# Beta0_1_5_Schematic_diagram.net
KiCad netlist of a schematic drawn in Altium Designer
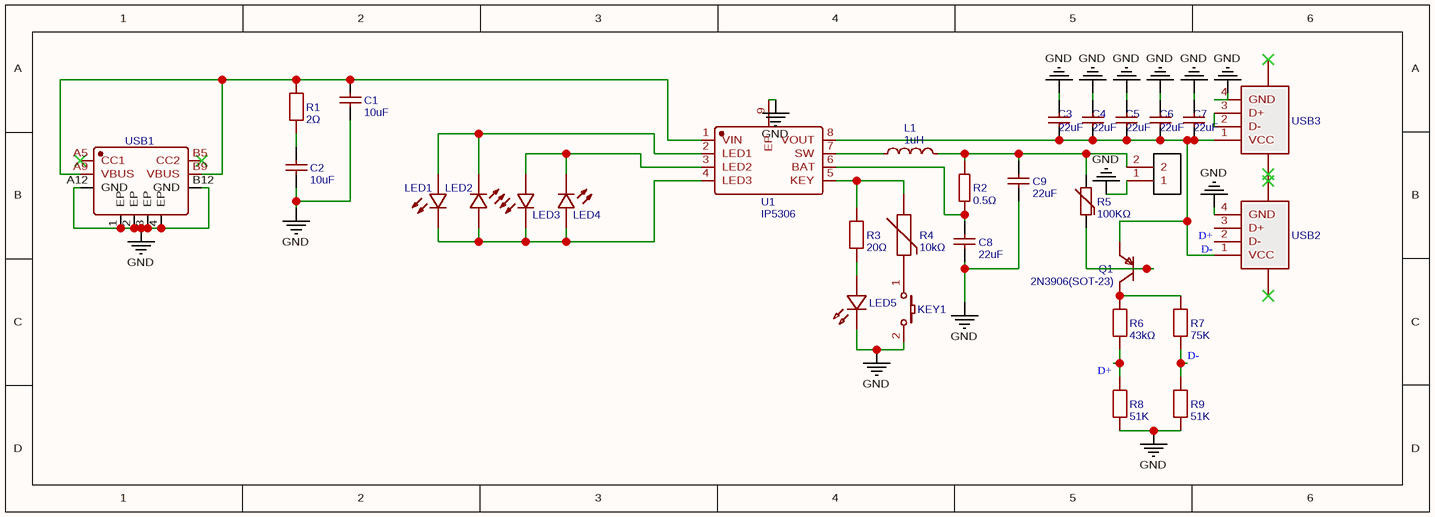
[diagram p0: Beta0.1.5 Schematic diagram.schdoc]

(export (version "E")
  (design (tool "Eeschema 10.0.6"))
  (components
    (comp (ref "C1")
      (value "10uF")
      (fields
        (field (name "BOM_MANUFACTURER PART") "CL31A106KBHNNNE")
        (field (name "BOM_SUPPLIER PART") "C13585")
      )
      (libsource (lib "altium-import") (part "root_3_10uF_"))
    )
    (comp (ref "C2")
      (value "10uF")
      (fields
        (field (name "BOM_MANUFACTURER PART") "CL31A106KBHNNNE")
        (field (name "BOM_SUPPLIER PART") "C13585")
      )
      (libsource (lib "altium-import") (part "root_3_10uF_"))
    )
    (comp (ref "C3")
      (value "22uF")
      (fields
        (field (name "BOM_MANUFACTURER PART") "CL31A226KPHNNNE")
        (field (name "BOM_SUPPLIER PART") "C5672")
      )
      (libsource (lib "altium-import") (part "root_1_22uF_"))
    )
    (comp (ref "C4")
      (value "22uF")
      (fields
        (field (name "BOM_MANUFACTURER PART") "CL31A226KPHNNNE")
        (field (name "BOM_SUPPLIER PART") "C5672")
      )
      (libsource (lib "altium-import") (part "root_1_22uF_"))
    )
    (comp (ref "C5")
      (value "22uF")
      (fields
        (field (name "BOM_MANUFACTURER PART") "CL31A226KPHNNNE")
        (field (name "BOM_SUPPLIER PART") "C5672")
      )
      (libsource (lib "altium-import") (part "root_1_22uF_"))
    )
    (comp (ref "C6")
      (value "22uF")
      (fields
        (field (name "BOM_MANUFACTURER PART") "CL31A226KPHNNNE")
        (field (name "BOM_SUPPLIER PART") "C5672")
      )
      (libsource (lib "altium-import") (part "root_1_22uF_"))
    )
    (comp (ref "C7")
      (value "22uF")
      (fields
        (field (name "BOM_MANUFACTURER PART") "CL31A226KPHNNNE")
        (field (name "BOM_SUPPLIER PART") "C5672")
      )
      (libsource (lib "altium-import") (part "root_1_22uF_"))
    )
    (comp (ref "C8")
      (value "22uF")
      (fields
        (field (name "BOM_MANUFACTURER PART") "CL31A226KPHNNNE")
        (field (name "BOM_SUPPLIER PART") "C5672")
      )
      (libsource (lib "altium-import") (part "root_1_22uF_"))
    )
    (comp (ref "C9")
      (value "22uF")
      (fields
        (field (name "BOM_MANUFACTURER PART") "CL31A226KPHNNNE")
        (field (name "BOM_SUPPLIER PART") "C5672")
      )
      (libsource (lib "altium-import") (part "root_1_22uF_"))
    )
    (comp (ref "CN1")
      (value "254010-02A-T0P")
      (fields (field (name "BOM_SUPPLIER PART") "C181912") (field (name "CONTRIBUTOR") "LCSC"))
      (libsource (lib "altium-import") (part "root_1_254010-02A-T0P_"))
    )
    (comp (ref "KEY1")
      (value "K2-3.6×6.1_SMD")
      (fields
        (field (name "BOM_SUPPLIER PART") "C118141")
        (field (name "BOM_MANUFACTURER PART") "K2-1107ST-A4SW-06")
        (field (name "CONTRIBUTOR") "LCEDA_Lib")
      )
      (libsource (lib "altium-import") (part "root_3_K2-3.6×6.1_SMD_"))
    )
    (comp (ref "L1")
      (value "1uH")
      (fields
        (field (name "BOM_MANUFACTURER PART") "SPM6530T-1R0M120")
        (field (name "BOM_SUPPLIER PART") "C87572")
      )
      (libsource (lib "altium-import") (part "root_0_1uH_"))
    )
    (comp (ref "LED1")
      (value "LED1")
      (fields
        (field (name "BOM_MANUFACTURER PART") "FC-DA1608HRK-620D")
        (field (name "BOM_SUPPLIER PART") "C84263")
      )
      (libsource (lib "altium-import") (part "root_3_LED1_"))
    )
    (comp (ref "LED2")
      (value "LED1")
      (fields
        (field (name "BOM_MANUFACTURER PART") "FC-DA1608HRK-620D")
        (field (name "BOM_SUPPLIER PART") "C84263")
      )
      (libsource (lib "altium-import") (part "root_1_LED1_"))
    )
    (comp (ref "LED3")
      (value "LED1")
      (fields
        (field (name "BOM_MANUFACTURER PART") "FC-DA1608HRK-620D")
        (field (name "BOM_SUPPLIER PART") "C84263")
      )
      (libsource (lib "altium-import") (part "root_3_LED1_"))
    )
    (comp (ref "LED4")
      (value "LED1")
      (fields
        (field (name "BOM_MANUFACTURER PART") "FC-DA1608HRK-620D")
        (field (name "BOM_SUPPLIER PART") "C84263")
      )
      (libsource (lib "altium-import") (part "root_1_LED1_"))
    )
    (comp (ref "LED5")
      (value "TZ-P2-1206WYCS2-0.9T")
      (fields (field (name "BOM_SUPPLIER PART") "C779809") (field (name "CONTRIBUTOR") "LCSC"))
      (libsource (lib "altium-import") (part "root_1_TZ-P2-1206WYCS2-0.9T_"))
    )
    (comp (ref "Q1")
      (value "2N3906(SOT-23)")
      (fields
        (field (name "BOM_MANUFACTURER PART") "2N3906S-RTK/PS")
        (field (name "BOM_SUPPLIER PART") "C147294")
        (field (name "CONTRIBUTOR") "LCEDA_Lib")
      )
      (libsource (lib "altium-import") (part "root_0_2N3906(SOT-23)_"))
    )
    (comp (ref "R1")
      (value "2Ω")
      (fields
        (field (name "BOM_SUPPLIER PART") "C723696")
        (field (name "BOM_MANUFACTURER PART") "RT0603BRD072RL")
        (field (name "CONTRIBUTOR") "LCSC")
      )
      (libsource (lib "altium-import") (part "root_3_2Ω_"))
    )
    (comp (ref "R2")
      (value "0.5Ω")
      (fields
        (field (name "BOM_SUPPLIER PART") "C270967")
        (field (name "BOM_MANUFACTURER PART") "201007F500LT4E")
        (field (name "CONTRIBUTOR") "LCSC")
      )
      (libsource (lib "altium-import") (part "root_1_0.5Ω_"))
    )
    (comp (ref "R3")
      (value "20Ω")
      (fields
        (field (name "BOM_SUPPLIER PART") "C313703")
        (field (name "BOM_MANUFACTURER PART") "CRCW060320R0FKEAHP")
        (field (name "CONTRIBUTOR") "lcsc")
      )
      (libsource (lib "altium-import") (part "root_1_20Ω_"))
    )
    (comp (ref "R4")
      (value "10kΩ")
      (fields
        (field (name "BOM_MANUFACTURER PART") "B57221V2103J060")
        (field (name "BOM_SUPPLIER PART") "C117695")
      )
      (libsource (lib "altium-import") (part "root_1_10kΩ_"))
    )
    (comp (ref "R5")
      (value "100KΩ")
      (fields
        (field (name "BOM_MANUFACTURER PART") "SDNT1608X104J4250HTF")
        (field (name "BOM_SUPPLIER PART") "C92368")
      )
      (libsource (lib "altium-import") (part "root_1_100KΩ_"))
    )
    (comp (ref "R6")
      (value "43kΩ")
      (fields
        (field (name "BOM_SUPPLIER PART") "C421987")
        (field (name "BOM_MANUFACTURER PART") "181207J0433T4E")
        (field (name "CONTRIBUTOR") "LCSC")
      )
      (libsource (lib "altium-import") (part "root_1_43kΩ_"))
    )
    (comp (ref "R7")
      (value "75K")
      (fields
        (field (name "BOM_SUPPLIER PART") "C230492")
        (field (name "BOM_MANUFACTURER PART") "AC1210JR-0775KL")
        (field (name "CONTRIBUTOR") "LCSC")
      )
      (libsource (lib "altium-import") (part "root_1_75K_"))
    )
    (comp (ref "R8")
      (value "51K")
      (fields
        (field (name "BOM_SUPPLIER PART") "C226721")
        (field (name "BOM_MANUFACTURER PART") "AC0402DR-0751KL")
        (field (name "CONTRIBUTOR") "LCSC")
      )
      (libsource (lib "altium-import") (part "root_1_51K_"))
    )
    (comp (ref "R9")
      (value "51K")
      (fields
        (field (name "BOM_SUPPLIER PART") "C226721")
        (field (name "BOM_MANUFACTURER PART") "AC0402DR-0751KL")
        (field (name "CONTRIBUTOR") "LCSC")
      )
      (libsource (lib "altium-import") (part "root_1_51K_"))
    )
    (comp (ref "U1")
      (value "IP5306")
      (fields (field (name "BOM_SUPPLIER PART") "C181692") (field (name "CONTRIBUTOR") "LCSC"))
      (libsource (lib "altium-import") (part "root_0_IP5306_"))
    )
    (comp (ref "USB1")
      (value "KH-TYPE-C-6P-T")
      (fields (field (name "BOM_SUPPLIER PART") "C709356") (field (name "CONTRIBUTOR") "LCSC"))
      (libsource (lib "altium-import") (part "root_0_KH-TYPE-C-6P-T_"))
    )
    (comp (ref "USB2")
      (value "292303-1")
      (fields (field (name "BOM_SUPPLIER PART") "C86461"))
      (libsource (lib "altium-import") (part "root_2_292303-1_"))
    )
    (comp (ref "USB3")
      (value "292303-1")
      (fields (field (name "BOM_SUPPLIER PART") "C86461"))
      (libsource (lib "altium-import") (part "root_2_292303-1_"))
    )
  )
  (nets
    (net (code "1") (name "/D+") (class "Default")
      (node (ref "R6") (pin "1") (pinfunction "1_1") (pintype "passive"))
      (node (ref "R8") (pin "2") (pinfunction "2_2") (pintype "passive"))
      (node (ref "USB2") (pin "3") (pinfunction "D+_3") (pintype "passive"))
    )
    (net (code "2") (name "/D-") (class "Default")
      (node (ref "R7") (pin "1") (pinfunction "1_1") (pintype "passive"))
      (node (ref "R9") (pin "2") (pinfunction "2_2") (pintype "passive"))
      (node (ref "USB2") (pin "2") (pinfunction "D-_2") (pintype "passive"))
    )
    (net (code "3") (name "GND") (class "Default")
      (node (ref "C1") (pin "2") (pinfunction "2_2") (pintype "passive"))
      (node (ref "C2") (pin "2") (pinfunction "2_2") (pintype "passive"))
      (node (ref "C3") (pin "2") (pinfunction "2_2") (pintype "passive"))
      (node (ref "C4") (pin "2") (pinfunction "2_2") (pintype "passive"))
      (node (ref "C5") (pin "2") (pinfunction "2_2") (pintype "passive"))
      (node (ref "C6") (pin "2") (pinfunction "2_2") (pintype "passive"))
      (node (ref "C7") (pin "2") (pinfunction "2_2") (pintype "passive"))
      (node (ref "C8") (pin "1") (pinfunction "1_1") (pintype "passive"))
      (node (ref "C9") (pin "1") (pinfunction "1_1") (pintype "passive"))
      (node (ref "CN1") (pin "1") (pinfunction "1_1") (pintype "passive"))
      (node (ref "KEY1") (pin "2") (pinfunction "2_2") (pintype "passive"))
      (node (ref "LED5") (pin "1") (pinfunction "K_1") (pintype "passive"))
      (node (ref "R8") (pin "1") (pinfunction "1_1") (pintype "passive"))
      (node (ref "R9") (pin "1") (pinfunction "1_1") (pintype "passive"))
      (node (ref "U1") (pin "9") (pinfunction "EP_9") (pintype "passive"))
      (node (ref "USB1") (pin "1") (pinfunction "EP_1") (pintype "passive"))
      (node (ref "USB1") (pin "2") (pinfunction "EP_2") (pintype "passive"))
      (node (ref "USB1") (pin "3") (pinfunction "EP_3") (pintype "passive"))
      (node (ref "USB1") (pin "4") (pinfunction "EP_4") (pintype "passive"))
      (node (ref "USB1") (pin "A12") (pinfunction "GND_A12") (pintype "passive"))
      (node (ref "USB1") (pin "B12") (pinfunction "GND_B12") (pintype "passive"))
      (node (ref "USB2") (pin "4") (pinfunction "GND_4") (pintype "passive"))
      (node (ref "USB3") (pin "4") (pinfunction "GND_4") (pintype "passive"))
    )
    (net (code "4") (name "Net-(C2-Pad1)") (class "Default")
      (node (ref "C2") (pin "1") (pinfunction "1_1") (pintype "passive"))
      (node (ref "R1") (pin "2") (pinfunction "2_2") (pintype "passive"))
    )
    (net (code "5") (name "Net-(C9-Pad2)") (class "Default")
      (node (ref "C9") (pin "2") (pinfunction "2_2") (pintype "passive"))
      (node (ref "CN1") (pin "2") (pinfunction "2_2") (pintype "passive"))
      (node (ref "L1") (pin "2") (pinfunction "2_2") (pintype "passive"))
      (node (ref "R2") (pin "2") (pinfunction "2_2") (pintype "passive"))
      (node (ref "R5") (pin "2") (pinfunction "2_2") (pintype "passive"))
    )
    (net (code "6") (name "Net-(KEY1-Pad1)") (class "Default")
      (node (ref "KEY1") (pin "1") (pinfunction "1_1") (pintype "passive"))
      (node (ref "R4") (pin "1") (pinfunction "1_1") (pintype "passive"))
    )
    (net (code "7") (name "Net-(LED1-A)") (class "Default")
      (node (ref "LED1") (pin "1") (pinfunction "A_1") (pintype "passive"))
      (node (ref "LED2") (pin "2") (pinfunction "K_2") (pintype "passive"))
      (node (ref "U1") (pin "2") (pinfunction "LED1_2") (pintype "passive"))
    )
    (net (code "8") (name "Net-(LED1-K)") (class "Default")
      (node (ref "LED1") (pin "2") (pinfunction "K_2") (pintype "passive"))
      (node (ref "LED2") (pin "1") (pinfunction "A_1") (pintype "passive"))
      (node (ref "LED3") (pin "2") (pinfunction "K_2") (pintype "passive"))
      (node (ref "LED4") (pin "1") (pinfunction "A_1") (pintype "passive"))
      (node (ref "U1") (pin "4") (pinfunction "LED3_4") (pintype "passive"))
    )
    (net (code "9") (name "Net-(LED3-A)") (class "Default")
      (node (ref "LED3") (pin "1") (pinfunction "A_1") (pintype "passive"))
      (node (ref "LED4") (pin "2") (pinfunction "K_2") (pintype "passive"))
      (node (ref "U1") (pin "3") (pinfunction "LED2_3") (pintype "passive"))
    )
    (net (code "10") (name "Net-(LED5-A)") (class "Default")
      (node (ref "LED5") (pin "2") (pinfunction "A_2") (pintype "passive"))
      (node (ref "R3") (pin "1") (pinfunction "1_1") (pintype "passive"))
    )
    (net (code "11") (name "Net-(Q1-B)") (class "Default")
      (node (ref "Q1") (pin "2") (pinfunction "B_2") (pintype "passive"))
      (node (ref "R5") (pin "1") (pinfunction "1_1") (pintype "passive"))
    )
    (net (code "12") (name "Net-(Q1-C)") (class "Default")
      (node (ref "Q1") (pin "3") (pinfunction "C_3") (pintype "passive"))
      (node (ref "R6") (pin "2") (pinfunction "2_2") (pintype "passive"))
      (node (ref "R7") (pin "2") (pinfunction "2_2") (pintype "passive"))
    )
    (net (code "13") (name "Net-(Q1-E)") (class "Default")
      (node (ref "C3") (pin "1") (pinfunction "1_1") (pintype "passive"))
      (node (ref "C4") (pin "1") (pinfunction "1_1") (pintype "passive"))
      (node (ref "C5") (pin "1") (pinfunction "1_1") (pintype "passive"))
      (node (ref "C6") (pin "1") (pinfunction "1_1") (pintype "passive"))
      (node (ref "C7") (pin "1") (pinfunction "1_1") (pintype "passive"))
      (node (ref "Q1") (pin "1") (pinfunction "E_1") (pintype "passive"))
      (node (ref "U1") (pin "8") (pinfunction "VOUT_8") (pintype "passive"))
      (node (ref "USB2") (pin "1") (pinfunction "VCC_1") (pintype "passive"))
      (node (ref "USB3") (pin "1") (pinfunction "VCC_1") (pintype "passive"))
    )
    (net (code "14") (name "Net-(U1-BAT)") (class "Default")
      (node (ref "C8") (pin "2") (pinfunction "2_2") (pintype "passive"))
      (node (ref "R2") (pin "1") (pinfunction "1_1") (pintype "passive"))
      (node (ref "U1") (pin "6") (pinfunction "BAT_6") (pintype "passive"))
    )
    (net (code "15") (name "Net-(U1-KEY)") (class "Default")
      (node (ref "R3") (pin "2") (pinfunction "2_2") (pintype "passive"))
      (node (ref "R4") (pin "2") (pinfunction "2_2") (pintype "passive"))
      (node (ref "U1") (pin "5") (pinfunction "KEY_5") (pintype "passive"))
    )
    (net (code "16") (name "Net-(U1-SW)") (class "Default")
      (node (ref "L1") (pin "1") (pinfunction "1_1") (pintype "passive"))
      (node (ref "U1") (pin "7") (pinfunction "SW_7") (pintype "passive"))
    )
    (net (code "17") (name "Net-(U1-VIN)") (class "Default")
      (node (ref "C1") (pin "1") (pinfunction "1_1") (pintype "passive"))
      (node (ref "R1") (pin "1") (pinfunction "1_1") (pintype "passive"))
      (node (ref "U1") (pin "1") (pinfunction "VIN_1") (pintype "passive"))
      (node (ref "USB1") (pin "A9") (pinfunction "VBUS_A9") (pintype "passive"))
      (node (ref "USB1") (pin "B9") (pinfunction "VBUS_B9") (pintype "passive"))
    )
    (net (code "18") (name "Net-(USB3-D+)") (class "Default")
      (node (ref "USB3") (pin "2") (pinfunction "D-_2") (pintype "passive"))
      (node (ref "USB3") (pin "3") (pinfunction "D+_3") (pintype "passive"))
    )
    (net (code "19") (name "unconnected-(USB1-CC1-PadA5)") (class "Default")
      (node (ref "USB1") (pin "A5") (pinfunction "CC1_A5") (pintype "passive+no_connect"))
    )
    (net (code "20") (name "unconnected-(USB1-CC2-PadB5)") (class "Default")
      (node (ref "USB1") (pin "B5") (pinfunction "CC2_B5") (pintype "passive+no_connect"))
    )
    (net (code "21") (name "unconnected-(USB2-Pad5)") (class "Default")
      (node (ref "USB2") (pin "5") (pinfunction "5_5") (pintype "passive+no_connect"))
    )
    (net (code "22") (name "unconnected-(USB2-Pad6)") (class "Default")
      (node (ref "USB2") (pin "6") (pinfunction "6_6") (pintype "passive+no_connect"))
    )
    (net (code "23") (name "unconnected-(USB3-Pad5)") (class "Default")
      (node (ref "USB3") (pin "5") (pinfunction "5_5") (pintype "passive+no_connect"))
    )
    (net (code "24") (name "unconnected-(USB3-Pad6)") (class "Default")
      (node (ref "USB3") (pin "6") (pinfunction "6_6") (pintype "passive+no_connect"))
    )
  )
)
